# MCU_LF.net
KiCad netlist of a schematic drawn in Altium Designer
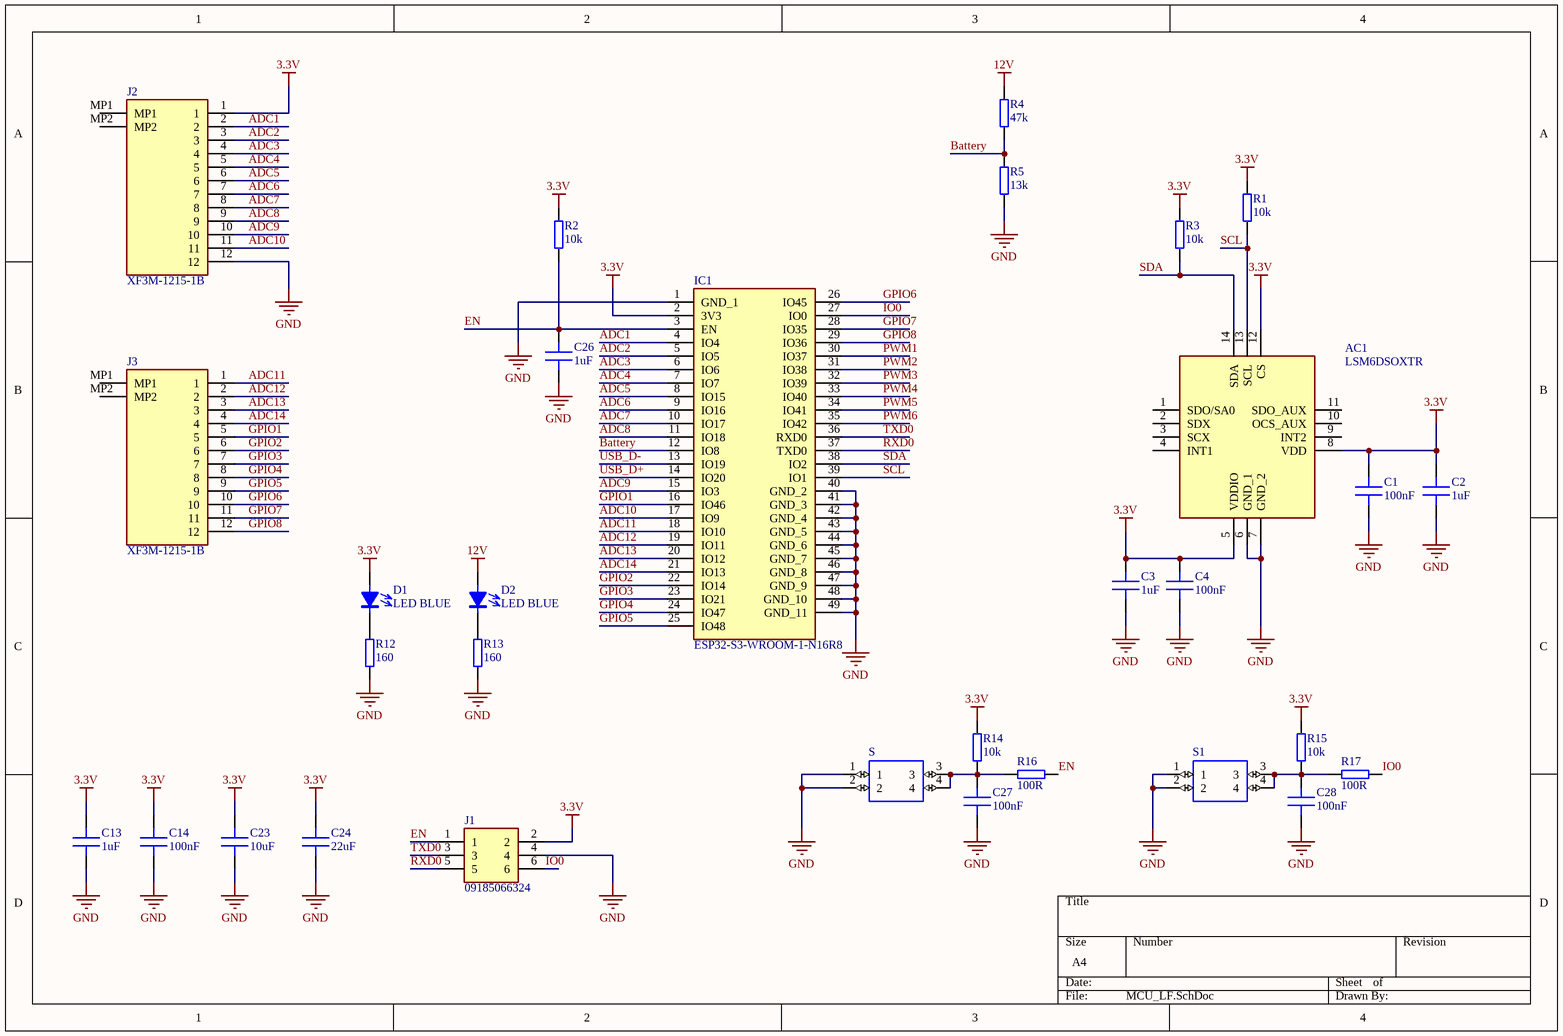
[diagram p0: MCU_LF.SchDoc]

(export (version "E")
  (design (tool "Eeschema 10.0.6"))
  (components
    (comp (ref "AC1")
      (value "LSM6DSOXTR")
      (footprint "SamacSys:LGA-14_1")
      (description "Accelerometer")
      (fields (field (name "MOUSER PART NUMBER") "511-LSM6DSOXTR"))
      (libsource (lib "lf_esp_sch_lib") (part "LSM6DSOXTR"))
    )
    (comp (ref "C1")
      (value "100nF")
      (footprint "C 0402")
      (description "MLCC Capacitor")
      (libsource (lib "Components") (part "Capacitor"))
    )
    (comp (ref "C2")
      (value "1uF")
      (footprint "C 0402")
      (description "MLCC Capacitor")
      (libsource (lib "Components") (part "Capacitor"))
    )
    (comp (ref "C3")
      (value "1uF")
      (footprint "C 0402")
      (description "MLCC Capacitor")
      (libsource (lib "Components") (part "Capacitor"))
    )
    (comp (ref "C4")
      (value "100nF")
      (footprint "C 0402")
      (description "MLCC Capacitor")
      (libsource (lib "Components") (part "Capacitor"))
    )
    (comp (ref "C13")
      (value "1uF")
      (footprint "C 0402")
      (description "MLCC Capacitor")
      (libsource (lib "Components") (part "Capacitor"))
    )
    (comp (ref "C14")
      (value "100nF")
      (footprint "C 0402")
      (description "MLCC Capacitor")
      (libsource (lib "Components") (part "Capacitor"))
    )
    (comp (ref "C23")
      (value "10uF")
      (footprint "C 0402")
      (description "MLCC Capacitor")
      (libsource (lib "Components") (part "Capacitor"))
    )
    (comp (ref "C24")
      (value "22uF")
      (footprint "C 0402")
      (description "MLCC Capacitor")
      (libsource (lib "Components") (part "Capacitor"))
    )
    (comp (ref "C26")
      (value "1uF")
      (footprint "C 0402")
      (description "MLCC Capacitor")
      (libsource (lib "Components") (part "Capacitor"))
    )
    (comp (ref "C27")
      (value "100nF")
      (footprint "C 0402")
      (description "MLCC Capacitor")
      (libsource (lib "Components") (part "Capacitor"))
    )
    (comp (ref "C28")
      (value "100nF")
      (footprint "C 0402")
      (description "MLCC Capacitor")
      (libsource (lib "Components") (part "Capacitor"))
    )
    (comp (ref "D1")
      (value "LED BLUE")
      (footprint "LED 0603 BLUE")
      (libsource (lib "Components") (part "LED BLUE"))
    )
    (comp (ref "D2")
      (value "LED BLUE")
      (footprint "LED 0603 BLUE")
      (libsource (lib "Components") (part "LED BLUE"))
    )
    (comp (ref "IC1")
      (value "ESP32-S3-WROOM-1-N16R8")
      (footprint "lf_esp_pcb_lib:ESP32S3WROOM1N16R8")
      (description "Integrated Circuit")
      (fields (field (name "MOUSER PART NUMBER") "356-ESP32S3WRM1N16R8"))
      (libsource (lib "lf_esp_sch_lib") (part "ESP32-S3-WROOM-1-N16R8"))
    )
    (comp (ref "J1")
      (value "09185066324")
      (footprint "SamacSys:09185066324")
      (description "Connector")
      (fields (field (name "MOUSER PART NUMBER") "617-09185066324"))
      (libsource (lib "lf_esp_sch_lib") (part "09185066324"))
    )
    (comp (ref "J2")
      (value "XF3M-1215-1B")
      (footprint "SamacSys:XF3M12151B")
      (description "Connector")
      (fields (field (name "MOUSER PART NUMBER") "653-XF3M-1215-1B"))
      (libsource (lib "lf_esp_sch_lib") (part "XF3M-1215-1B"))
    )
    (comp (ref "J3")
      (value "XF3M-1215-1B")
      (footprint "SamacSys:XF3M12151B")
      (description "Connector")
      (fields (field (name "MOUSER PART NUMBER") "653-XF3M-1215-1B"))
      (libsource (lib "lf_esp_sch_lib") (part "XF3M-1215-1B"))
    )
    (comp (ref "R1")
      (value "10k")
      (footprint "R 0402")
      (description "General pourpouse resistor")
      (libsource (lib "Components") (part "Resistor"))
    )
    (comp (ref "R2")
      (value "10k")
      (footprint "R 0402")
      (description "General pourpouse resistor")
      (libsource (lib "Components") (part "Resistor"))
    )
    (comp (ref "R3")
      (value "10k")
      (footprint "R 0402")
      (description "General pourpouse resistor")
      (libsource (lib "Components") (part "Resistor"))
    )
    (comp (ref "R4")
      (value "47k")
      (footprint "R 0402")
      (description "General pourpouse resistor")
      (libsource (lib "Components") (part "Resistor"))
    )
    (comp (ref "R5")
      (value "13k")
      (footprint "R 0402")
      (description "General pourpouse resistor")
      (libsource (lib "Components") (part "Resistor"))
    )
    (comp (ref "R12")
      (value "160")
      (footprint "R 0402")
      (description "General pourpouse resistor")
      (libsource (lib "Components") (part "Resistor"))
    )
    (comp (ref "R13")
      (value "160")
      (footprint "R 0402")
      (description "General pourpouse resistor")
      (libsource (lib "Components") (part "Resistor"))
    )
    (comp (ref "R14")
      (value "10k")
      (footprint "R 0402")
      (description "General pourpouse resistor")
      (libsource (lib "Components") (part "Resistor"))
    )
    (comp (ref "R15")
      (value "10k")
      (footprint "R 0402")
      (description "General pourpouse resistor")
      (libsource (lib "Components") (part "Resistor"))
    )
    (comp (ref "R16")
      (value "100R")
      (footprint "R 0402")
      (description "General pourpouse resistor")
      (libsource (lib "Components") (part "Resistor"))
    )
    (comp (ref "R17")
      (value "100R")
      (footprint "R 0402")
      (description "General pourpouse resistor")
      (libsource (lib "Components") (part "Resistor"))
    )
    (comp (ref "S")
      (value "PTS810SJK250SMTRLFS")
      (footprint "PTS810SJG250SMTRLFS")
      (description "Tactile Switch SPST-NO Top Actuated Surface Mount")
      (fields (field (name "MF") "C&K"))
      (libsource (lib "PTS810SJK250SMTRLFS") (part "PTS810SJK250SMTRLFS"))
    )
    (comp (ref "S1")
      (value "PTS810SJK250SMTRLFS")
      (footprint "PTS810SJG250SMTRLFS")
      (description "Tactile Switch SPST-NO Top Actuated Surface Mount")
      (fields (field (name "MF") "C&K"))
      (libsource (lib "PTS810SJK250SMTRLFS") (part "PTS810SJK250SMTRLFS"))
    )
  )
  (nets
    (net (code "1") (name "/ADC1") (class "Default")
      (node (ref "IC1") (pin "4") (pinfunction "IO4_4") (pintype "passive"))
      (node (ref "J2") (pin "2") (pinfunction "2_2") (pintype "passive"))
    )
    (net (code "2") (name "/ADC2") (class "Default")
      (node (ref "IC1") (pin "5") (pinfunction "IO5_5") (pintype "passive"))
      (node (ref "J2") (pin "3") (pinfunction "3_3") (pintype "passive"))
    )
    (net (code "3") (name "/ADC3") (class "Default")
      (node (ref "IC1") (pin "6") (pinfunction "IO6_6") (pintype "passive"))
      (node (ref "J2") (pin "4") (pinfunction "4_4") (pintype "passive"))
    )
    (net (code "4") (name "/ADC4") (class "Default")
      (node (ref "IC1") (pin "7") (pinfunction "IO7_7") (pintype "passive"))
      (node (ref "J2") (pin "5") (pinfunction "5_5") (pintype "passive"))
    )
    (net (code "5") (name "/ADC5") (class "Default")
      (node (ref "IC1") (pin "8") (pinfunction "IO15_8") (pintype "passive"))
      (node (ref "J2") (pin "6") (pinfunction "6_6") (pintype "passive"))
    )
    (net (code "6") (name "/ADC6") (class "Default")
      (node (ref "IC1") (pin "9") (pinfunction "IO16_9") (pintype "passive"))
      (node (ref "J2") (pin "7") (pinfunction "7_7") (pintype "passive"))
    )
    (net (code "7") (name "/ADC7") (class "Default")
      (node (ref "IC1") (pin "10") (pinfunction "IO17_10") (pintype "passive"))
      (node (ref "J2") (pin "8") (pinfunction "8_8") (pintype "passive"))
    )
    (net (code "8") (name "/ADC8") (class "Default")
      (node (ref "IC1") (pin "11") (pinfunction "IO18_11") (pintype "passive"))
      (node (ref "J2") (pin "9") (pinfunction "9_9") (pintype "passive"))
    )
    (net (code "9") (name "/ADC9") (class "Default")
      (node (ref "IC1") (pin "15") (pinfunction "IO3_15") (pintype "passive"))
      (node (ref "J2") (pin "10") (pinfunction "10_10") (pintype "passive"))
    )
    (net (code "10") (name "/ADC10") (class "Default")
      (node (ref "IC1") (pin "17") (pinfunction "IO9_17") (pintype "passive"))
      (node (ref "J2") (pin "11") (pinfunction "11_11") (pintype "passive"))
    )
    (net (code "11") (name "/ADC11") (class "Default")
      (node (ref "IC1") (pin "18") (pinfunction "IO10_18") (pintype "passive"))
      (node (ref "J3") (pin "1") (pinfunction "1_1") (pintype "passive"))
    )
    (net (code "12") (name "/ADC12") (class "Default")
      (node (ref "IC1") (pin "19") (pinfunction "IO11_19") (pintype "passive"))
      (node (ref "J3") (pin "2") (pinfunction "2_2") (pintype "passive"))
    )
    (net (code "13") (name "/ADC13") (class "Default")
      (node (ref "IC1") (pin "20") (pinfunction "IO12_20") (pintype "passive"))
      (node (ref "J3") (pin "3") (pinfunction "3_3") (pintype "passive"))
    )
    (net (code "14") (name "/ADC14") (class "Default")
      (node (ref "IC1") (pin "21") (pinfunction "IO13_21") (pintype "passive"))
      (node (ref "J3") (pin "4") (pinfunction "4_4") (pintype "passive"))
    )
    (net (code "15") (name "/Battery") (class "Default")
      (node (ref "IC1") (pin "12") (pinfunction "IO8_12") (pintype "passive"))
      (node (ref "R4") (pin "1") (pinfunction "1_1") (pintype "passive"))
      (node (ref "R5") (pin "2") (pinfunction "2_2") (pintype "passive"))
    )
    (net (code "16") (name "/EN") (class "Default")
      (node (ref "C26") (pin "1") (pinfunction "1_1") (pintype "passive"))
      (node (ref "IC1") (pin "3") (pinfunction "EN_3") (pintype "passive"))
      (node (ref "J1") (pin "1") (pinfunction "1_1") (pintype "passive"))
      (node (ref "R16") (pin "1") (pinfunction "1_1") (pintype "passive"))
      (node (ref "R2") (pin "1") (pinfunction "1_1") (pintype "passive"))
    )
    (net (code "17") (name "/GPIO1") (class "Default")
      (node (ref "IC1") (pin "16") (pinfunction "IO46_16") (pintype "passive"))
      (node (ref "J3") (pin "5") (pinfunction "5_5") (pintype "passive"))
    )
    (net (code "18") (name "/GPIO2") (class "Default")
      (node (ref "IC1") (pin "22") (pinfunction "IO14_22") (pintype "passive"))
      (node (ref "J3") (pin "6") (pinfunction "6_6") (pintype "passive"))
    )
    (net (code "19") (name "/GPIO3") (class "Default")
      (node (ref "IC1") (pin "23") (pinfunction "IO21_23") (pintype "passive"))
      (node (ref "J3") (pin "7") (pinfunction "7_7") (pintype "passive"))
    )
    (net (code "20") (name "/GPIO4") (class "Default")
      (node (ref "IC1") (pin "24") (pinfunction "IO47_24") (pintype "passive"))
      (node (ref "J3") (pin "8") (pinfunction "8_8") (pintype "passive"))
    )
    (net (code "21") (name "/GPIO5") (class "Default")
      (node (ref "IC1") (pin "25") (pinfunction "IO48_25") (pintype "passive"))
      (node (ref "J3") (pin "9") (pinfunction "9_9") (pintype "passive"))
    )
    (net (code "22") (name "/GPIO6") (class "Default")
      (node (ref "IC1") (pin "26") (pinfunction "IO45_26") (pintype "passive"))
      (node (ref "J3") (pin "10") (pinfunction "10_10") (pintype "passive"))
    )
    (net (code "23") (name "/GPIO7") (class "Default")
      (node (ref "IC1") (pin "28") (pinfunction "IO35_28") (pintype "passive"))
      (node (ref "J3") (pin "11") (pinfunction "11_11") (pintype "passive"))
    )
    (net (code "24") (name "/GPIO8") (class "Default")
      (node (ref "IC1") (pin "29") (pinfunction "IO36_29") (pintype "passive"))
      (node (ref "J3") (pin "12") (pinfunction "12_12") (pintype "passive"))
    )
    (net (code "25") (name "/IO0") (class "Default")
      (node (ref "IC1") (pin "27") (pinfunction "IO0_27") (pintype "passive"))
      (node (ref "J1") (pin "6") (pinfunction "6_6") (pintype "passive"))
      (node (ref "R17") (pin "1") (pinfunction "1_1") (pintype "passive"))
    )
    (net (code "26") (name "/PWM1") (class "Default")
      (node (ref "IC1") (pin "30") (pinfunction "IO37_30") (pintype "passive"))
    )
    (net (code "27") (name "/PWM2") (class "Default")
      (node (ref "IC1") (pin "31") (pinfunction "IO38_31") (pintype "passive"))
    )
    (net (code "28") (name "/PWM3") (class "Default")
      (node (ref "IC1") (pin "32") (pinfunction "IO39_32") (pintype "passive"))
    )
    (net (code "29") (name "/PWM4") (class "Default")
      (node (ref "IC1") (pin "33") (pinfunction "IO40_33") (pintype "passive"))
    )
    (net (code "30") (name "/PWM5") (class "Default")
      (node (ref "IC1") (pin "34") (pinfunction "IO41_34") (pintype "passive"))
    )
    (net (code "31") (name "/PWM6") (class "Default")
      (node (ref "IC1") (pin "35") (pinfunction "IO42_35") (pintype "passive"))
    )
    (net (code "32") (name "/RXD0") (class "Default")
      (node (ref "IC1") (pin "37") (pinfunction "TXD0_37") (pintype "passive"))
      (node (ref "J1") (pin "5") (pinfunction "5_5") (pintype "passive"))
    )
    (net (code "33") (name "/SCL") (class "Default")
      (node (ref "AC1") (pin "13") (pinfunction "SCL_13") (pintype "passive"))
      (node (ref "IC1") (pin "39") (pinfunction "IO1_39") (pintype "passive"))
      (node (ref "R1") (pin "1") (pinfunction "1_1") (pintype "passive"))
    )
    (net (code "34") (name "/SDA") (class "Default")
      (node (ref "AC1") (pin "14") (pinfunction "SDA_14") (pintype "passive"))
      (node (ref "IC1") (pin "38") (pinfunction "IO2_38") (pintype "passive"))
      (node (ref "R3") (pin "1") (pinfunction "1_1") (pintype "passive"))
    )
    (net (code "35") (name "/TXD0") (class "Default")
      (node (ref "IC1") (pin "36") (pinfunction "RXD0_36") (pintype "passive"))
      (node (ref "J1") (pin "3") (pinfunction "3_3") (pintype "passive"))
    )
    (net (code "36") (name "/USB_D+") (class "Default")
      (node (ref "IC1") (pin "14") (pinfunction "IO20_14") (pintype "passive"))
    )
    (net (code "37") (name "/USB_D-") (class "Default")
      (node (ref "IC1") (pin "13") (pinfunction "IO19_13") (pintype "passive"))
    )
    (net (code "38") (name "3.3V") (class "Default")
      (node (ref "AC1") (pin "12") (pinfunction "CS_12") (pintype "passive"))
      (node (ref "AC1") (pin "5") (pinfunction "VDDIO_5") (pintype "passive"))
      (node (ref "AC1") (pin "8") (pinfunction "VDD_8") (pintype "passive"))
      (node (ref "C1") (pin "1") (pinfunction "1_1") (pintype "passive"))
      (node (ref "C13") (pin "1") (pinfunction "1_1") (pintype "passive"))
      (node (ref "C14") (pin "1") (pinfunction "1_1") (pintype "passive"))
      (node (ref "C2") (pin "1") (pinfunction "1_1") (pintype "passive"))
      (node (ref "C23") (pin "1") (pinfunction "1_1") (pintype "passive"))
      (node (ref "C24") (pin "1") (pinfunction "1_1") (pintype "passive"))
      (node (ref "C3") (pin "1") (pinfunction "1_1") (pintype "passive"))
      (node (ref "C4") (pin "1") (pinfunction "1_1") (pintype "passive"))
      (node (ref "D1") (pin "1") (pinfunction "1_1") (pintype "passive"))
      (node (ref "IC1") (pin "2") (pinfunction "3V3_2") (pintype "passive"))
      (node (ref "J1") (pin "2") (pinfunction "2_2") (pintype "passive"))
      (node (ref "J2") (pin "1") (pinfunction "1_1") (pintype "passive"))
      (node (ref "R1") (pin "2") (pinfunction "2_2") (pintype "passive"))
      (node (ref "R14") (pin "2") (pinfunction "2_2") (pintype "passive"))
      (node (ref "R15") (pin "2") (pinfunction "2_2") (pintype "passive"))
      (node (ref "R2") (pin "2") (pinfunction "2_2") (pintype "passive"))
      (node (ref "R3") (pin "2") (pinfunction "2_2") (pintype "passive"))
    )
    (net (code "39") (name "12V") (class "Default")
      (node (ref "D2") (pin "1") (pinfunction "1_1") (pintype "passive"))
      (node (ref "R4") (pin "2") (pinfunction "2_2") (pintype "passive"))
    )
    (net (code "40") (name "GND") (class "Default")
      (node (ref "AC1") (pin "6") (pinfunction "GND_1_6") (pintype "passive"))
      (node (ref "AC1") (pin "7") (pinfunction "GND_2_7") (pintype "passive"))
      (node (ref "C1") (pin "2") (pinfunction "2_2") (pintype "passive"))
      (node (ref "C13") (pin "2") (pinfunction "2_2") (pintype "passive"))
      (node (ref "C14") (pin "2") (pinfunction "2_2") (pintype "passive"))
      (node (ref "C2") (pin "2") (pinfunction "2_2") (pintype "passive"))
      (node (ref "C23") (pin "2") (pinfunction "2_2") (pintype "passive"))
      (node (ref "C24") (pin "2") (pinfunction "2_2") (pintype "passive"))
      (node (ref "C26") (pin "2") (pinfunction "2_2") (pintype "passive"))
      (node (ref "C27") (pin "2") (pinfunction "2_2") (pintype "passive"))
      (node (ref "C28") (pin "2") (pinfunction "2_2") (pintype "passive"))
      (node (ref "C3") (pin "2") (pinfunction "2_2") (pintype "passive"))
      (node (ref "C4") (pin "2") (pinfunction "2_2") (pintype "passive"))
      (node (ref "IC1") (pin "1") (pinfunction "GND_1_1") (pintype "passive"))
      (node (ref "IC1") (pin "40") (pinfunction "GND_2_40") (pintype "passive"))
      (node (ref "IC1") (pin "41") (pinfunction "GND_3_41") (pintype "passive"))
      (node (ref "IC1") (pin "42") (pinfunction "GND_4_42") (pintype "passive"))
      (node (ref "IC1") (pin "43") (pinfunction "GND_5_43") (pintype "passive"))
      (node (ref "IC1") (pin "44") (pinfunction "GND_6_44") (pintype "passive"))
      (node (ref "IC1") (pin "45") (pinfunction "GND_7_45") (pintype "passive"))
      (node (ref "IC1") (pin "46") (pinfunction "GND_8_46") (pintype "passive"))
      (node (ref "IC1") (pin "47") (pinfunction "GND_9_47") (pintype "passive"))
      (node (ref "IC1") (pin "48") (pinfunction "GND_10_48") (pintype "passive"))
      (node (ref "IC1") (pin "49") (pinfunction "GND_11_49") (pintype "passive"))
      (node (ref "J1") (pin "4") (pinfunction "4_4") (pintype "passive"))
      (node (ref "J2") (pin "12") (pinfunction "12_12") (pintype "passive"))
      (node (ref "R12") (pin "1") (pinfunction "1_1") (pintype "passive"))
      (node (ref "R13") (pin "1") (pinfunction "1_1") (pintype "passive"))
      (node (ref "R5") (pin "1") (pinfunction "1_1") (pintype "passive"))
      (node (ref "S") (pin "1") (pinfunction "1_1") (pintype "bidirectional"))
      (node (ref "S") (pin "2") (pinfunction "2_2") (pintype "bidirectional"))
      (node (ref "S1") (pin "1") (pinfunction "1_1") (pintype "bidirectional"))
      (node (ref "S1") (pin "2") (pinfunction "2_2") (pintype "bidirectional"))
    )
    (net (code "41") (name "Net-(C27-Pad1)") (class "Default")
      (node (ref "C27") (pin "1") (pinfunction "1_1") (pintype "passive"))
      (node (ref "R14") (pin "1") (pinfunction "1_1") (pintype "passive"))
      (node (ref "R16") (pin "2") (pinfunction "2_2") (pintype "passive"))
      (node (ref "S") (pin "3") (pinfunction "3_3") (pintype "bidirectional"))
      (node (ref "S") (pin "4") (pinfunction "4_4") (pintype "bidirectional"))
    )
    (net (code "42") (name "Net-(C28-Pad1)") (class "Default")
      (node (ref "C28") (pin "1") (pinfunction "1_1") (pintype "passive"))
      (node (ref "R15") (pin "1") (pinfunction "1_1") (pintype "passive"))
      (node (ref "R17") (pin "2") (pinfunction "2_2") (pintype "passive"))
      (node (ref "S1") (pin "3") (pinfunction "3_3") (pintype "bidirectional"))
      (node (ref "S1") (pin "4") (pinfunction "4_4") (pintype "bidirectional"))
    )
    (net (code "43") (name "Net-(D1-Pad2)") (class "Default")
      (node (ref "D1") (pin "2") (pinfunction "2_2") (pintype "passive"))
      (node (ref "R12") (pin "2") (pinfunction "2_2") (pintype "passive"))
    )
    (net (code "44") (name "Net-(D2-Pad2)") (class "Default")
      (node (ref "D2") (pin "2") (pinfunction "2_2") (pintype "passive"))
      (node (ref "R13") (pin "2") (pinfunction "2_2") (pintype "passive"))
    )
    (net (code "45") (name "unconnected-(AC1-INT1-Pad4)") (class "Default")
      (node (ref "AC1") (pin "4") (pinfunction "INT1_4") (pintype "passive"))
    )
    (net (code "46") (name "unconnected-(AC1-INT2-Pad9)") (class "Default")
      (node (ref "AC1") (pin "9") (pinfunction "INT2_9") (pintype "passive"))
    )
    (net (code "47") (name "unconnected-(AC1-OCS_AUX-Pad10)") (class "Default")
      (node (ref "AC1") (pin "10") (pinfunction "OCS_AUX_10") (pintype "passive"))
    )
    (net (code "48") (name "unconnected-(AC1-SCX-Pad3)") (class "Default")
      (node (ref "AC1") (pin "3") (pinfunction "SCX_3") (pintype "passive"))
    )
    (net (code "49") (name "unconnected-(AC1-SDO_AUX-Pad11)") (class "Default")
      (node (ref "AC1") (pin "11") (pinfunction "SDO_AUX_11") (pintype "passive"))
    )
    (net (code "50") (name "unconnected-(AC1-SDO{slash}SA0-Pad1)") (class "Default")
      (node (ref "AC1") (pin "1") (pinfunction "SDO/SA0_1") (pintype "passive"))
    )
    (net (code "51") (name "unconnected-(AC1-SDX-Pad2)") (class "Default")
      (node (ref "AC1") (pin "2") (pinfunction "SDX_2") (pintype "passive"))
    )
    (net (code "52") (name "unconnected-(J2-PadMP1)") (class "Default")
      (node (ref "J2") (pin "MP1") (pinfunction "MP1_MP1") (pintype "passive"))
    )
    (net (code "53") (name "unconnected-(J2-PadMP2)") (class "Default")
      (node (ref "J2") (pin "MP2") (pinfunction "MP2_MP2") (pintype "passive"))
    )
    (net (code "54") (name "unconnected-(J3-PadMP1)") (class "Default")
      (node (ref "J3") (pin "MP1") (pinfunction "MP1_MP1") (pintype "passive"))
    )
    (net (code "55") (name "unconnected-(J3-PadMP2)") (class "Default")
      (node (ref "J3") (pin "MP2") (pinfunction "MP2_MP2") (pintype "passive"))
    )
  )
)
